# KMP-Watermeter-Schematic.net
KiCad netlist of a schematic drawn in Altium Designer
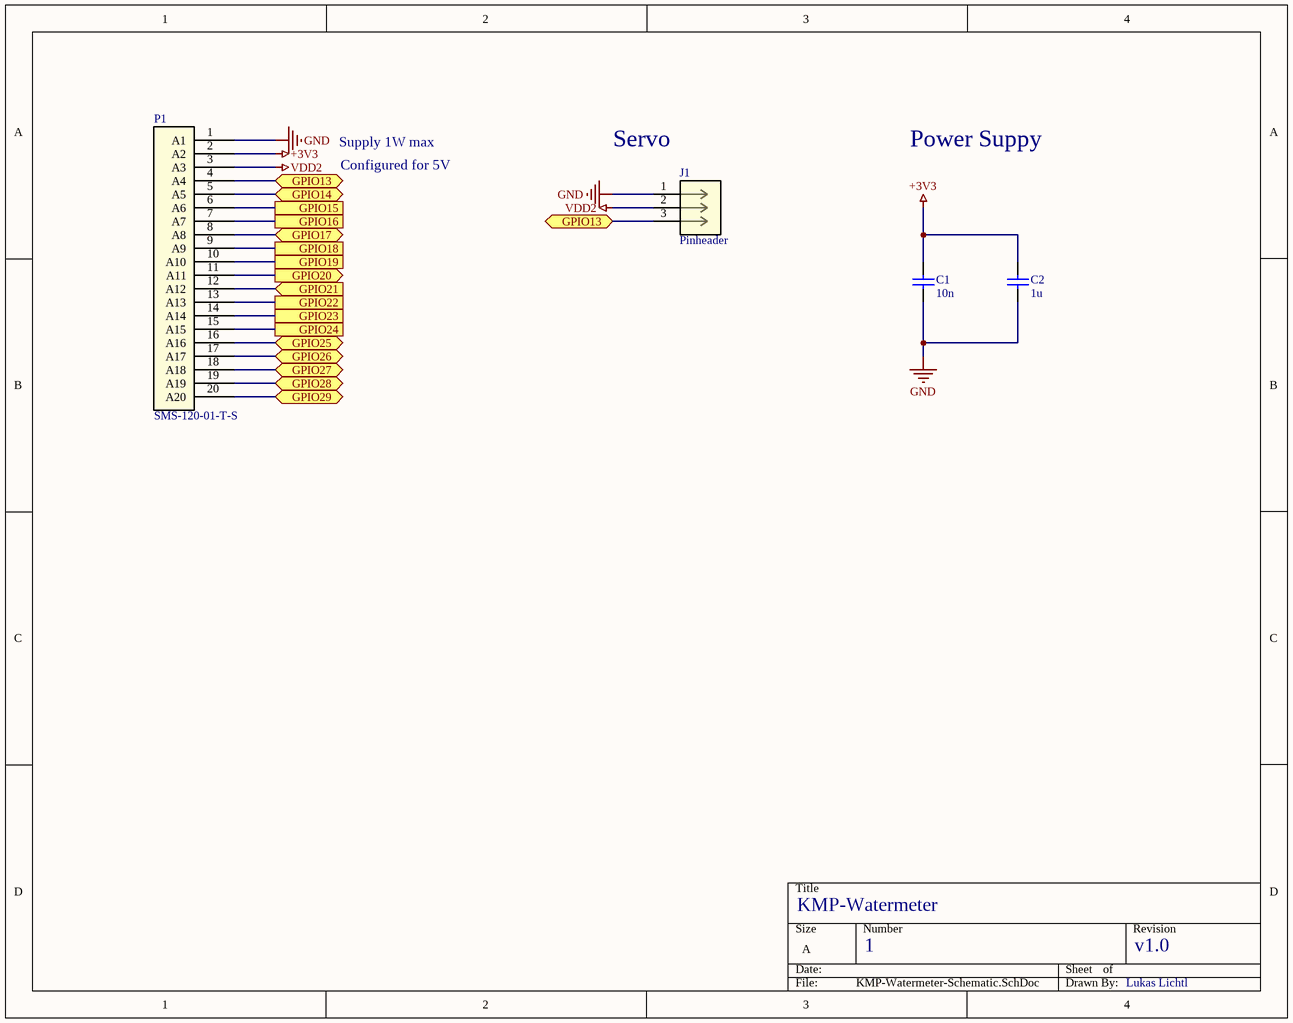
[diagram p0: KMP-Watermeter-Schematic.SchDoc]

(export (version "E")
  (design (tool "Eeschema 10.0.6"))
  (components
    (comp (ref "C1")
      (value "10n")
      (footprint "CAPC1608X90X35LL15T15")
      (fields
        (field (name "MANUFACTURER") "AVX Interconnect / Elco")
        (field (name "PART NUMBER") "0603ZC101KAT2A")
      )
      (libsource (lib "Altium Content Vault") (part "CAP"))
    )
    (comp (ref "C2")
      (value "1u")
      (footprint "CAPC1608X90X35LL15T15")
      (fields
        (field (name "MANUFACTURER") "AVX Interconnect / Elco")
        (field (name "PART NUMBER") "0603ZC101KAT2A")
      )
      (libsource (lib "Altium Content Vault") (part "CAP"))
    )
    (comp (ref "J1")
      (value "Pinheader")
      (footprint "CONN03_6130_7P62X2P54_WRE")
      (description "WR-PHD 2.54 mm Pin Header")
      (fields
        (field (name "MANUFACTURER_PART_NUMBER") "61300311121")
        (field (name "COPYRIGHT") "Copyright (C) 2026 Ultra Librarian. All rights reserved.")
      )
      (libsource (lib "Servo_Pinheader") (part "61300311121"))
    )
    (comp (ref "P1")
      (value "SMS-120-01-T-S")
      (footprint "SMS-S-120")
      (description "No Description Available")
      (libsource (lib "SMS-120-01-T-S") (part "SMS-120-01-T-S"))
    )
  )
  (nets
    (net (code "1") (name "+3V3") (class "Default")
      (node (ref "C1") (pin "2") (pinfunction "2_2") (pintype "passive"))
      (node (ref "C2") (pin "2") (pinfunction "2_2") (pintype "passive"))
      (node (ref "P1") (pin "2") (pinfunction "A2_2") (pintype "passive"))
    )
    (net (code "2") (name "/GPIO13") (class "Default")
      (node (ref "J1") (pin "3") (pinfunction "3_3") (pintype "passive"))
      (node (ref "P1") (pin "4") (pinfunction "A4_4") (pintype "passive"))
    )
    (net (code "3") (name "/GPIO14") (class "Default")
      (node (ref "P1") (pin "5") (pinfunction "A5_5") (pintype "passive"))
    )
    (net (code "4") (name "/GPIO15") (class "Default")
      (node (ref "P1") (pin "6") (pinfunction "A6_6") (pintype "passive"))
    )
    (net (code "5") (name "/GPIO16") (class "Default")
      (node (ref "P1") (pin "7") (pinfunction "A7_7") (pintype "passive"))
    )
    (net (code "6") (name "/GPIO17") (class "Default")
      (node (ref "P1") (pin "8") (pinfunction "A8_8") (pintype "passive"))
    )
    (net (code "7") (name "/GPIO18") (class "Default")
      (node (ref "P1") (pin "9") (pinfunction "A9_9") (pintype "passive"))
    )
    (net (code "8") (name "/GPIO19") (class "Default")
      (node (ref "P1") (pin "10") (pinfunction "A10_10") (pintype "passive"))
    )
    (net (code "9") (name "/GPIO20") (class "Default")
      (node (ref "P1") (pin "11") (pinfunction "A11_11") (pintype "passive"))
    )
    (net (code "10") (name "/GPIO21") (class "Default")
      (node (ref "P1") (pin "12") (pinfunction "A12_12") (pintype "passive"))
    )
    (net (code "11") (name "/GPIO22") (class "Default")
      (node (ref "P1") (pin "13") (pinfunction "A13_13") (pintype "passive"))
    )
    (net (code "12") (name "/GPIO23") (class "Default")
      (node (ref "P1") (pin "14") (pinfunction "A14_14") (pintype "passive"))
    )
    (net (code "13") (name "/GPIO24") (class "Default")
      (node (ref "P1") (pin "15") (pinfunction "A15_15") (pintype "passive"))
    )
    (net (code "14") (name "/GPIO25") (class "Default")
      (node (ref "P1") (pin "16") (pinfunction "A16_16") (pintype "passive"))
    )
    (net (code "15") (name "/GPIO26") (class "Default")
      (node (ref "P1") (pin "17") (pinfunction "A17_17") (pintype "passive"))
    )
    (net (code "16") (name "/GPIO27") (class "Default")
      (node (ref "P1") (pin "18") (pinfunction "A18_18") (pintype "passive"))
    )
    (net (code "17") (name "/GPIO28") (class "Default")
      (node (ref "P1") (pin "19") (pinfunction "A19_19") (pintype "passive"))
    )
    (net (code "18") (name "/GPIO29") (class "Default")
      (node (ref "P1") (pin "20") (pinfunction "A20_20") (pintype "passive"))
    )
    (net (code "19") (name "GND") (class "Default")
      (node (ref "C1") (pin "1") (pinfunction "1_1") (pintype "passive"))
      (node (ref "C2") (pin "1") (pinfunction "1_1") (pintype "passive"))
      (node (ref "J1") (pin "1") (pinfunction "1_1") (pintype "passive"))
      (node (ref "P1") (pin "1") (pinfunction "A1_1") (pintype "passive"))
    )
    (net (code "20") (name "VDD2") (class "Default")
      (node (ref "J1") (pin "2") (pinfunction "2_2") (pintype "passive"))
      (node (ref "P1") (pin "3") (pinfunction "A3_3") (pintype "passive"))
    )
  )
)
